# FlexiblePart.net
KiCad netlist of a schematic drawn in Altium Designer
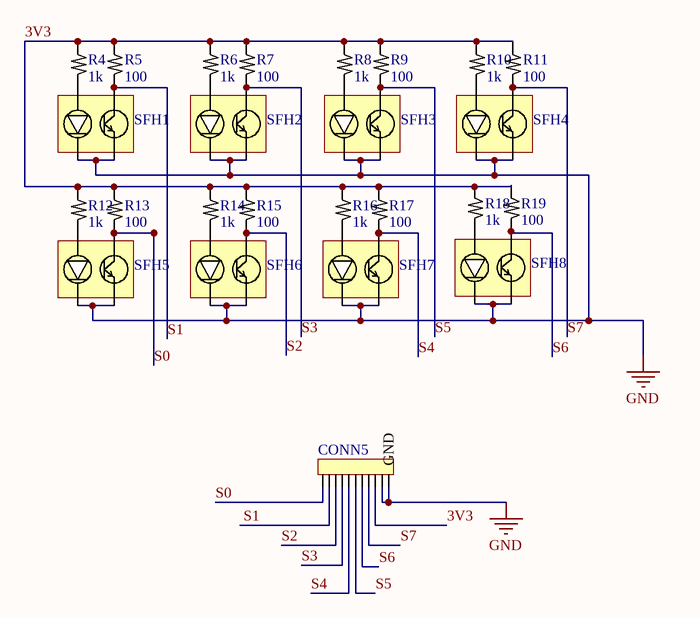
[diagram p0: FlexiblePart.SchDoc]

(export (version "E")
  (design (tool "Eeschema 10.0.6"))
  (components
    (comp (ref "CONN5")
      (value "10_pin_connector")
      (footprint "10Pin_1mmpitch_FFC_FCP_ZIF")
      (description "10 Pin Connector")
      (libsource (lib "ARMBand_Components") (part "10_pin_connector"))
    )
    (comp (ref "R4")
      (value "1k")
      (footprint "Resistor_1608")
      (description "SMD Resistor")
      (libsource (lib "ARMBand_Components") (part "Resistor_SMD"))
    )
    (comp (ref "R5")
      (value "100")
      (footprint "Resistor_1608")
      (description "SMD Resistor")
      (libsource (lib "ARMBand_Components") (part "Resistor_SMD"))
    )
    (comp (ref "R6")
      (value "1k")
      (footprint "Resistor_1608")
      (description "SMD Resistor")
      (libsource (lib "ARMBand_Components") (part "Resistor_SMD"))
    )
    (comp (ref "R7")
      (value "100")
      (footprint "Resistor_1608")
      (description "SMD Resistor")
      (libsource (lib "ARMBand_Components") (part "Resistor_SMD"))
    )
    (comp (ref "R8")
      (value "1k")
      (footprint "Resistor_1608")
      (description "SMD Resistor")
      (libsource (lib "ARMBand_Components") (part "Resistor_SMD"))
    )
    (comp (ref "R9")
      (value "100")
      (footprint "Resistor_1608")
      (description "SMD Resistor")
      (libsource (lib "ARMBand_Components") (part "Resistor_SMD"))
    )
    (comp (ref "R10")
      (value "1k")
      (footprint "Resistor_1608")
      (description "SMD Resistor")
      (libsource (lib "ARMBand_Components") (part "Resistor_SMD"))
    )
    (comp (ref "R11")
      (value "100")
      (footprint "Resistor_1608")
      (description "SMD Resistor")
      (libsource (lib "ARMBand_Components") (part "Resistor_SMD"))
    )
    (comp (ref "R12")
      (value "1k")
      (footprint "Resistor_1608")
      (description "SMD Resistor")
      (libsource (lib "ARMBand_Components") (part "Resistor_SMD"))
    )
    (comp (ref "R13")
      (value "100")
      (footprint "Resistor_1608")
      (description "SMD Resistor")
      (libsource (lib "ARMBand_Components") (part "Resistor_SMD"))
    )
    (comp (ref "R14")
      (value "1k")
      (footprint "Resistor_1608")
      (description "SMD Resistor")
      (libsource (lib "ARMBand_Components") (part "Resistor_SMD"))
    )
    (comp (ref "R15")
      (value "100")
      (footprint "Resistor_1608")
      (description "SMD Resistor")
      (libsource (lib "ARMBand_Components") (part "Resistor_SMD"))
    )
    (comp (ref "R16")
      (value "1k")
      (footprint "Resistor_1608")
      (description "SMD Resistor")
      (libsource (lib "ARMBand_Components") (part "Resistor_SMD"))
    )
    (comp (ref "R17")
      (value "100")
      (footprint "Resistor_1608")
      (description "SMD Resistor")
      (libsource (lib "ARMBand_Components") (part "Resistor_SMD"))
    )
    (comp (ref "R18")
      (value "1k")
      (footprint "Resistor_1608")
      (description "SMD Resistor")
      (libsource (lib "ARMBand_Components") (part "Resistor_SMD"))
    )
    (comp (ref "R19")
      (value "100")
      (footprint "Resistor_1608")
      (description "SMD Resistor")
      (libsource (lib "ARMBand_Components") (part "Resistor_SMD"))
    )
    (comp (ref "SFH1")
      (value "SFH 7250")
      (footprint "SFH_SENSOR_34x30")
      (description "Infrared Emitter - PhTransistor Receiver")
      (libsource (lib "ARMBand_Components") (part "Photoreflector"))
    )
    (comp (ref "SFH2")
      (value "SFH 7250")
      (footprint "SFH_SENSOR_34x30")
      (description "Infrared Emitter - PhTransistor Receiver")
      (libsource (lib "ARMBand_Components") (part "Photoreflector"))
    )
    (comp (ref "SFH3")
      (value "SFH 7250")
      (footprint "SFH_SENSOR_34x30")
      (description "Infrared Emitter - PhTransistor Receiver")
      (libsource (lib "ARMBand_Components") (part "Photoreflector"))
    )
    (comp (ref "SFH4")
      (value "SFH 7250")
      (footprint "SFH_SENSOR_34x30")
      (description "Infrared Emitter - PhTransistor Receiver")
      (libsource (lib "ARMBand_Components") (part "Photoreflector"))
    )
    (comp (ref "SFH5")
      (value "SFH 7250")
      (footprint "SFH_SENSOR_34x30")
      (description "Infrared Emitter - PhTransistor Receiver")
      (libsource (lib "ARMBand_Components") (part "Photoreflector"))
    )
    (comp (ref "SFH6")
      (value "SFH 7250")
      (footprint "SFH_SENSOR_34x30")
      (description "Infrared Emitter - PhTransistor Receiver")
      (libsource (lib "ARMBand_Components") (part "Photoreflector"))
    )
    (comp (ref "SFH7")
      (value "SFH 7250")
      (footprint "SFH_SENSOR_34x30")
      (description "Infrared Emitter - PhTransistor Receiver")
      (libsource (lib "ARMBand_Components") (part "Photoreflector"))
    )
    (comp (ref "SFH8")
      (value "SFH 7250")
      (footprint "SFH_SENSOR_34x30")
      (description "Infrared Emitter - PhTransistor Receiver")
      (libsource (lib "ARMBand_Components") (part "Photoreflector"))
    )
  )
  (nets
    (net (code "1") (name "/3V3") (class "Default")
      (node (ref "CONN5") (pin "9") (pinfunction "9_9") (pintype "passive"))
      (node (ref "R10") (pin "Res_p1") (pinfunction "Res_p1_Res_p1") (pintype "passive"))
      (node (ref "R11") (pin "Res_p1") (pinfunction "Res_p1_Res_p1") (pintype "passive"))
      (node (ref "R12") (pin "Res_p1") (pinfunction "Res_p1_Res_p1") (pintype "passive"))
      (node (ref "R13") (pin "Res_p1") (pinfunction "Res_p1_Res_p1") (pintype "passive"))
      (node (ref "R14") (pin "Res_p1") (pinfunction "Res_p1_Res_p1") (pintype "passive"))
      (node (ref "R15") (pin "Res_p1") (pinfunction "Res_p1_Res_p1") (pintype "passive"))
      (node (ref "R16") (pin "Res_p1") (pinfunction "Res_p1_Res_p1") (pintype "passive"))
      (node (ref "R17") (pin "Res_p1") (pinfunction "Res_p1_Res_p1") (pintype "passive"))
      (node (ref "R18") (pin "Res_p1") (pinfunction "Res_p1_Res_p1") (pintype "passive"))
      (node (ref "R19") (pin "Res_p1") (pinfunction "Res_p1_Res_p1") (pintype "passive"))
      (node (ref "R4") (pin "Res_p1") (pinfunction "Res_p1_Res_p1") (pintype "passive"))
      (node (ref "R5") (pin "Res_p1") (pinfunction "Res_p1_Res_p1") (pintype "passive"))
      (node (ref "R6") (pin "Res_p1") (pinfunction "Res_p1_Res_p1") (pintype "passive"))
      (node (ref "R7") (pin "Res_p1") (pinfunction "Res_p1_Res_p1") (pintype "passive"))
      (node (ref "R8") (pin "Res_p1") (pinfunction "Res_p1_Res_p1") (pintype "passive"))
      (node (ref "R9") (pin "Res_p1") (pinfunction "Res_p1_Res_p1") (pintype "passive"))
    )
    (net (code "2") (name "/S0") (class "Default")
      (node (ref "CONN5") (pin "1") (pinfunction "1_1") (pintype "passive"))
      (node (ref "R13") (pin "Res_p2") (pinfunction "Res_p2_Res_p2") (pintype "passive"))
      (node (ref "SFH5") (pin "PhT_Collector") (pinfunction "PhT_Collector_PhT_Collector") (pintype "passive"))
    )
    (net (code "3") (name "/S1") (class "Default")
      (node (ref "CONN5") (pin "2") (pinfunction "2_2") (pintype "passive"))
      (node (ref "R5") (pin "Res_p2") (pinfunction "Res_p2_Res_p2") (pintype "passive"))
      (node (ref "SFH1") (pin "PhT_Collector") (pinfunction "PhT_Collector_PhT_Collector") (pintype "passive"))
    )
    (net (code "4") (name "/S2") (class "Default")
      (node (ref "CONN5") (pin "3") (pinfunction "3_3") (pintype "passive"))
      (node (ref "R15") (pin "Res_p2") (pinfunction "Res_p2_Res_p2") (pintype "passive"))
      (node (ref "SFH6") (pin "PhT_Collector") (pinfunction "PhT_Collector_PhT_Collector") (pintype "passive"))
    )
    (net (code "5") (name "/S3") (class "Default")
      (node (ref "CONN5") (pin "4") (pinfunction "4_4") (pintype "passive"))
      (node (ref "R7") (pin "Res_p2") (pinfunction "Res_p2_Res_p2") (pintype "passive"))
      (node (ref "SFH2") (pin "PhT_Collector") (pinfunction "PhT_Collector_PhT_Collector") (pintype "passive"))
    )
    (net (code "6") (name "/S4") (class "Default")
      (node (ref "CONN5") (pin "5") (pinfunction "5_5") (pintype "passive"))
      (node (ref "R17") (pin "Res_p2") (pinfunction "Res_p2_Res_p2") (pintype "passive"))
      (node (ref "SFH7") (pin "PhT_Collector") (pinfunction "PhT_Collector_PhT_Collector") (pintype "passive"))
    )
    (net (code "7") (name "/S5") (class "Default")
      (node (ref "CONN5") (pin "6") (pinfunction "6_6") (pintype "passive"))
      (node (ref "R9") (pin "Res_p2") (pinfunction "Res_p2_Res_p2") (pintype "passive"))
      (node (ref "SFH3") (pin "PhT_Collector") (pinfunction "PhT_Collector_PhT_Collector") (pintype "passive"))
    )
    (net (code "8") (name "/S6") (class "Default")
      (node (ref "CONN5") (pin "7") (pinfunction "7_7") (pintype "passive"))
      (node (ref "R19") (pin "Res_p2") (pinfunction "Res_p2_Res_p2") (pintype "passive"))
      (node (ref "SFH8") (pin "PhT_Collector") (pinfunction "PhT_Collector_PhT_Collector") (pintype "passive"))
    )
    (net (code "9") (name "/S7") (class "Default")
      (node (ref "CONN5") (pin "8") (pinfunction "8_8") (pintype "passive"))
      (node (ref "R11") (pin "Res_p2") (pinfunction "Res_p2_Res_p2") (pintype "passive"))
      (node (ref "SFH4") (pin "PhT_Collector") (pinfunction "PhT_Collector_PhT_Collector") (pintype "passive"))
    )
    (net (code "10") (name "GND") (class "Default")
      (node (ref "CONN5") (pin "10") (pinfunction "10_10") (pintype "passive"))
      (node (ref "CONN5") (pin "GND") (pinfunction "GND_GND") (pintype "passive"))
      (node (ref "SFH1") (pin "LED_Cathode") (pinfunction "LED_Cathode_LED_Cathode") (pintype "passive"))
      (node (ref "SFH1") (pin "PhT_Emitter") (pinfunction "PhT_Emitter_PhT_Emitter") (pintype "passive"))
      (node (ref "SFH2") (pin "LED_Cathode") (pinfunction "LED_Cathode_LED_Cathode") (pintype "passive"))
      (node (ref "SFH2") (pin "PhT_Emitter") (pinfunction "PhT_Emitter_PhT_Emitter") (pintype "passive"))
      (node (ref "SFH3") (pin "LED_Cathode") (pinfunction "LED_Cathode_LED_Cathode") (pintype "passive"))
      (node (ref "SFH3") (pin "PhT_Emitter") (pinfunction "PhT_Emitter_PhT_Emitter") (pintype "passive"))
      (node (ref "SFH4") (pin "LED_Cathode") (pinfunction "LED_Cathode_LED_Cathode") (pintype "passive"))
      (node (ref "SFH4") (pin "PhT_Emitter") (pinfunction "PhT_Emitter_PhT_Emitter") (pintype "passive"))
      (node (ref "SFH5") (pin "LED_Cathode") (pinfunction "LED_Cathode_LED_Cathode") (pintype "passive"))
      (node (ref "SFH5") (pin "PhT_Emitter") (pinfunction "PhT_Emitter_PhT_Emitter") (pintype "passive"))
      (node (ref "SFH6") (pin "LED_Cathode") (pinfunction "LED_Cathode_LED_Cathode") (pintype "passive"))
      (node (ref "SFH6") (pin "PhT_Emitter") (pinfunction "PhT_Emitter_PhT_Emitter") (pintype "passive"))
      (node (ref "SFH7") (pin "LED_Cathode") (pinfunction "LED_Cathode_LED_Cathode") (pintype "passive"))
      (node (ref "SFH7") (pin "PhT_Emitter") (pinfunction "PhT_Emitter_PhT_Emitter") (pintype "passive"))
      (node (ref "SFH8") (pin "LED_Cathode") (pinfunction "LED_Cathode_LED_Cathode") (pintype "passive"))
      (node (ref "SFH8") (pin "PhT_Emitter") (pinfunction "PhT_Emitter_PhT_Emitter") (pintype "passive"))
    )
    (net (code "11") (name "Net-(R4-PadRes_p2)") (class "Default")
      (node (ref "R4") (pin "Res_p2") (pinfunction "Res_p2_Res_p2") (pintype "passive"))
      (node (ref "SFH1") (pin "LED_Anode") (pinfunction "LED_Anode_LED_Anode") (pintype "passive"))
    )
    (net (code "12") (name "Net-(R6-PadRes_p2)") (class "Default")
      (node (ref "R6") (pin "Res_p2") (pinfunction "Res_p2_Res_p2") (pintype "passive"))
      (node (ref "SFH2") (pin "LED_Anode") (pinfunction "LED_Anode_LED_Anode") (pintype "passive"))
    )
    (net (code "13") (name "Net-(R8-PadRes_p2)") (class "Default")
      (node (ref "R8") (pin "Res_p2") (pinfunction "Res_p2_Res_p2") (pintype "passive"))
      (node (ref "SFH3") (pin "LED_Anode") (pinfunction "LED_Anode_LED_Anode") (pintype "passive"))
    )
    (net (code "14") (name "Net-(R10-PadRes_p2)") (class "Default")
      (node (ref "R10") (pin "Res_p2") (pinfunction "Res_p2_Res_p2") (pintype "passive"))
      (node (ref "SFH4") (pin "LED_Anode") (pinfunction "LED_Anode_LED_Anode") (pintype "passive"))
    )
    (net (code "15") (name "Net-(R12-PadRes_p2)") (class "Default")
      (node (ref "R12") (pin "Res_p2") (pinfunction "Res_p2_Res_p2") (pintype "passive"))
      (node (ref "SFH5") (pin "LED_Anode") (pinfunction "LED_Anode_LED_Anode") (pintype "passive"))
    )
    (net (code "16") (name "Net-(R14-PadRes_p2)") (class "Default")
      (node (ref "R14") (pin "Res_p2") (pinfunction "Res_p2_Res_p2") (pintype "passive"))
      (node (ref "SFH6") (pin "LED_Anode") (pinfunction "LED_Anode_LED_Anode") (pintype "passive"))
    )
    (net (code "17") (name "Net-(R16-PadRes_p2)") (class "Default")
      (node (ref "R16") (pin "Res_p2") (pinfunction "Res_p2_Res_p2") (pintype "passive"))
      (node (ref "SFH7") (pin "LED_Anode") (pinfunction "LED_Anode_LED_Anode") (pintype "passive"))
    )
    (net (code "18") (name "Net-(R18-PadRes_p2)") (class "Default")
      (node (ref "R18") (pin "Res_p2") (pinfunction "Res_p2_Res_p2") (pintype "passive"))
      (node (ref "SFH8") (pin "LED_Anode") (pinfunction "LED_Anode_LED_Anode") (pintype "passive"))
    )
  )
)
